# main.net
KiCad netlist of a schematic drawn in Altium Designer
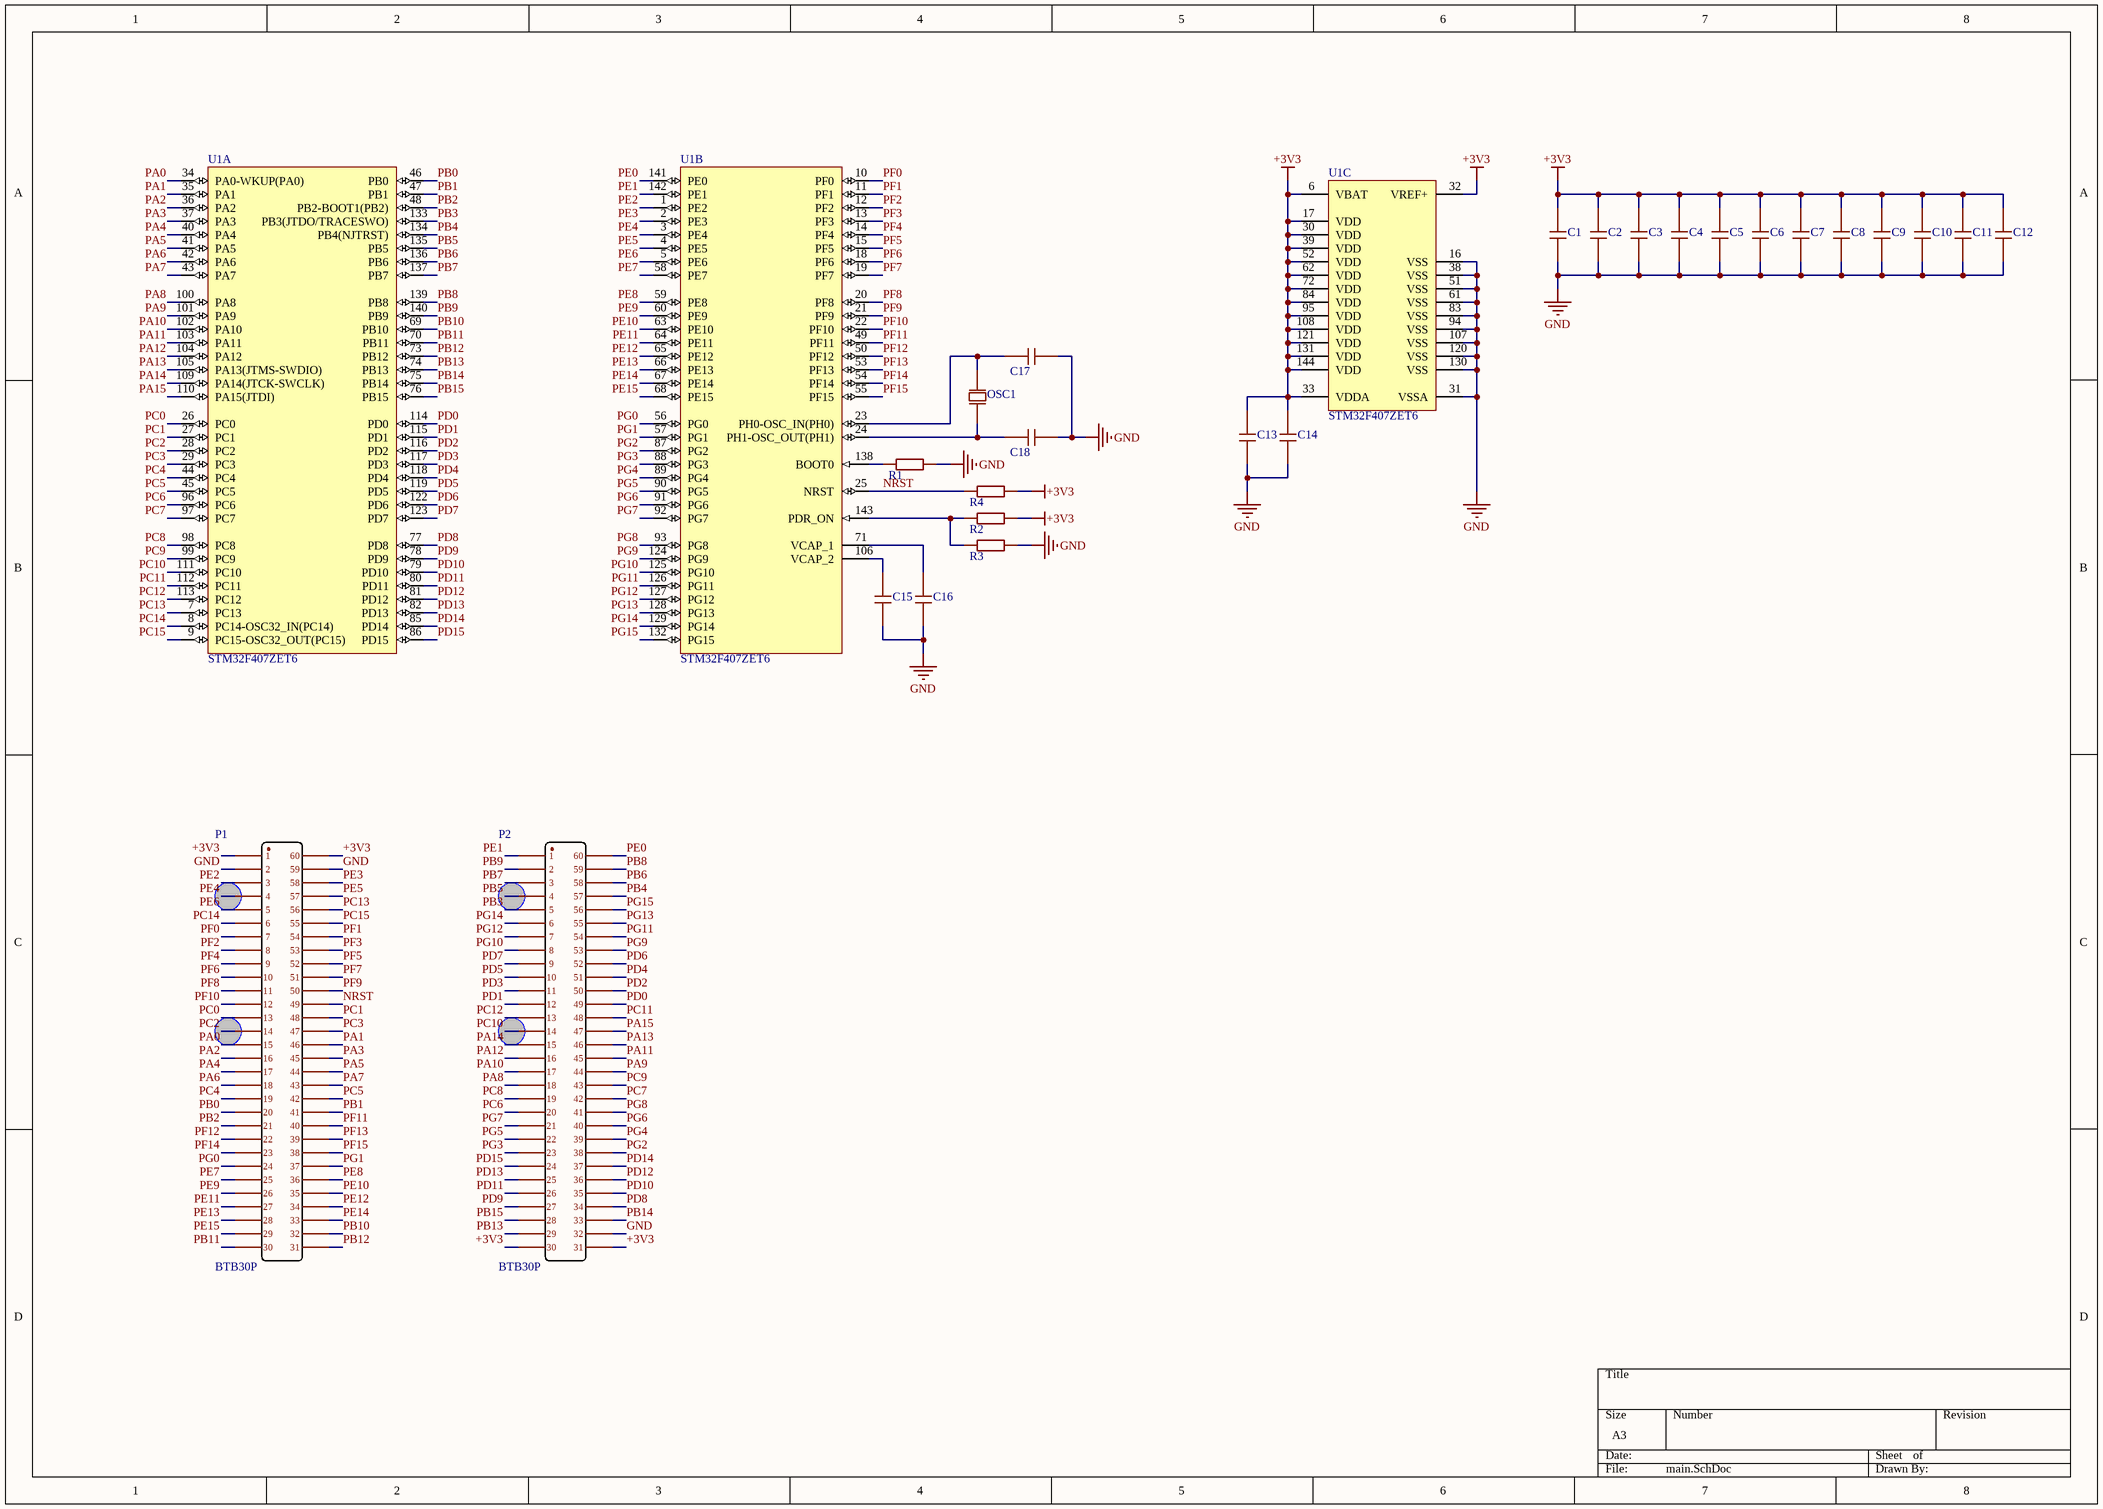
[diagram p0: main.SchDoc]

(export (version "E")
  (design (tool "Eeschema 10.0.6"))
  (components
    (comp (ref "C1") (value "100nF") (footprint "0603C") (libsource (lib "元件库") (part "电容_贴片")))
    (comp (ref "C2") (value "100nF") (footprint "0603C") (libsource (lib "元件库") (part "电容_贴片")))
    (comp (ref "C3") (value "100nF") (footprint "0603C") (libsource (lib "元件库") (part "电容_贴片")))
    (comp (ref "C4") (value "100nF") (footprint "0603C") (libsource (lib "元件库") (part "电容_贴片")))
    (comp (ref "C5") (value "100nF") (footprint "0603C") (libsource (lib "元件库") (part "电容_贴片")))
    (comp (ref "C6") (value "100nF") (footprint "0603C") (libsource (lib "元件库") (part "电容_贴片")))
    (comp (ref "C7") (value "100nF") (footprint "0603C") (libsource (lib "元件库") (part "电容_贴片")))
    (comp (ref "C8") (value "100nF") (footprint "0603C") (libsource (lib "元件库") (part "电容_贴片")))
    (comp (ref "C9") (value "100nF") (footprint "0603C") (libsource (lib "元件库") (part "电容_贴片")))
    (comp (ref "C10") (value "100nF") (footprint "0603C") (libsource (lib "元件库") (part "电容_贴片")))
    (comp (ref "C11") (value "100nF") (footprint "0603C") (libsource (lib "元件库") (part "电容_贴片")))
    (comp (ref "C12") (value "100nF") (footprint "0603C") (libsource (lib "元件库") (part "电容_贴片")))
    (comp (ref "C13") (value "10uF") (footprint "0603C") (libsource (lib "元件库") (part "电容_贴片")))
    (comp (ref "C14") (value "100nF") (footprint "0603C") (libsource (lib "元件库") (part "电容_贴片")))
    (comp (ref "C15") (value "2.2uF") (footprint "0603C") (libsource (lib "元件库") (part "电容_贴片")))
    (comp (ref "C16") (value "2.2uF") (footprint "0603C") (libsource (lib "元件库") (part "电容_贴片")))
    (comp (ref "C17") (value "20pF") (footprint "0603C") (libsource (lib "元件库") (part "电容_贴片")))
    (comp (ref "C18") (value "20pF") (footprint "0603C") (libsource (lib "元件库") (part "电容_贴片")))
    (comp (ref "OSC1") (value "晶振") (footprint "OSC_Passive_4P_3225") (libsource (lib "元件库") (part "晶振_无源")))
    (comp (ref "P1") (value "BTB30P") (footprint "BTB_F_30*2*0.8mm") (libsource (lib "接口库") (part "接插件2*30")))
    (comp (ref "P2") (value "BTB30P") (footprint "BTB_F_30*2*0.8mm") (libsource (lib "接口库") (part "接插件2*30")))
    (comp (ref "R1") (value "10K") (footprint "0603R") (libsource (lib "元件库") (part "电阻_贴片")))
    (comp (ref "R2") (value "10K") (footprint "0603R") (libsource (lib "元件库") (part "电阻_贴片")))
    (comp (ref "R3") (value "NC") (footprint "0603R") (libsource (lib "元件库") (part "电阻_贴片")))
    (comp (ref "R4") (value "10K") (footprint "0603R") (libsource (lib "元件库") (part "电阻_贴片")))
    (comp (ref "U1")
      (value "STM32F407ZET6")
      (footprint "STM-LQFP144")
      (fields (field (name "MANUFACTURER") "STMicroelectronics"))
      (libsource (lib "MCU库") (part "STM32F407ZET6"))
    )
  )
  (nets
    (net (code "1") (name "+3V3") (class "Default")
      (node (ref "C1") (pin "2") (pinfunction "2_2") (pintype "passive"))
      (node (ref "C10") (pin "2") (pinfunction "2_2") (pintype "passive"))
      (node (ref "C11") (pin "2") (pinfunction "2_2") (pintype "passive"))
      (node (ref "C12") (pin "2") (pinfunction "2_2") (pintype "passive"))
      (node (ref "C13") (pin "2") (pinfunction "2_2") (pintype "passive"))
      (node (ref "C14") (pin "2") (pinfunction "2_2") (pintype "passive"))
      (node (ref "C2") (pin "2") (pinfunction "2_2") (pintype "passive"))
      (node (ref "C3") (pin "2") (pinfunction "2_2") (pintype "passive"))
      (node (ref "C4") (pin "2") (pinfunction "2_2") (pintype "passive"))
      (node (ref "C5") (pin "2") (pinfunction "2_2") (pintype "passive"))
      (node (ref "C6") (pin "2") (pinfunction "2_2") (pintype "passive"))
      (node (ref "C7") (pin "2") (pinfunction "2_2") (pintype "passive"))
      (node (ref "C8") (pin "2") (pinfunction "2_2") (pintype "passive"))
      (node (ref "C9") (pin "2") (pinfunction "2_2") (pintype "passive"))
      (node (ref "P1") (pin "1") (pinfunction "1_1") (pintype "passive"))
      (node (ref "P1") (pin "60") (pinfunction "60_60") (pintype "passive"))
      (node (ref "P2") (pin "30") (pinfunction "30_30") (pintype "passive"))
      (node (ref "P2") (pin "31") (pinfunction "31_31") (pintype "passive"))
      (node (ref "R2") (pin "2") (pinfunction "2_2") (pintype "passive"))
      (node (ref "R4") (pin "2") (pinfunction "2_2") (pintype "passive"))
      (node (ref "U1") (pin "108") (pinfunction "VDD_108") (pintype "power_in"))
      (node (ref "U1") (pin "121") (pinfunction "VDD_121") (pintype "power_in"))
      (node (ref "U1") (pin "131") (pinfunction "VDD_131") (pintype "power_in"))
      (node (ref "U1") (pin "144") (pinfunction "VDD_144") (pintype "power_in"))
      (node (ref "U1") (pin "17") (pinfunction "VDD_17") (pintype "power_in"))
      (node (ref "U1") (pin "30") (pinfunction "VDD_30") (pintype "power_in"))
      (node (ref "U1") (pin "32") (pinfunction "VREF+_32") (pintype "power_in"))
      (node (ref "U1") (pin "33") (pinfunction "VDDA_33") (pintype "power_in"))
      (node (ref "U1") (pin "39") (pinfunction "VDD_39") (pintype "power_in"))
      (node (ref "U1") (pin "52") (pinfunction "VDD_52") (pintype "power_in"))
      (node (ref "U1") (pin "6") (pinfunction "VBAT_6") (pintype "power_in"))
      (node (ref "U1") (pin "62") (pinfunction "VDD_62") (pintype "power_in"))
      (node (ref "U1") (pin "72") (pinfunction "VDD_72") (pintype "power_in"))
      (node (ref "U1") (pin "84") (pinfunction "VDD_84") (pintype "power_in"))
      (node (ref "U1") (pin "95") (pinfunction "VDD_95") (pintype "power_in"))
    )
    (net (code "2") (name "/NRST") (class "Default")
      (node (ref "P1") (pin "49") (pinfunction "49_49") (pintype "passive"))
      (node (ref "R4") (pin "1") (pinfunction "1_1") (pintype "passive"))
      (node (ref "U1") (pin "25") (pinfunction "NRST_25") (pintype "bidirectional"))
    )
    (net (code "3") (name "/PA0") (class "Default")
      (node (ref "P1") (pin "15") (pinfunction "15_15") (pintype "passive"))
      (node (ref "U1") (pin "34") (pinfunction "PA0-WKUP(PA0)_34") (pintype "bidirectional"))
    )
    (net (code "4") (name "/PA1") (class "Default")
      (node (ref "P1") (pin "46") (pinfunction "46_46") (pintype "passive"))
      (node (ref "U1") (pin "35") (pinfunction "PA1_35") (pintype "bidirectional"))
    )
    (net (code "5") (name "/PA2") (class "Default")
      (node (ref "P1") (pin "16") (pinfunction "16_16") (pintype "passive"))
      (node (ref "U1") (pin "36") (pinfunction "PA2_36") (pintype "bidirectional"))
    )
    (net (code "6") (name "/PA3") (class "Default")
      (node (ref "P1") (pin "45") (pinfunction "45_45") (pintype "passive"))
      (node (ref "U1") (pin "37") (pinfunction "PA3_37") (pintype "bidirectional"))
    )
    (net (code "7") (name "/PA4") (class "Default")
      (node (ref "P1") (pin "17") (pinfunction "17_17") (pintype "passive"))
      (node (ref "U1") (pin "40") (pinfunction "PA4_40") (pintype "bidirectional"))
    )
    (net (code "8") (name "/PA5") (class "Default")
      (node (ref "P1") (pin "44") (pinfunction "44_44") (pintype "passive"))
      (node (ref "U1") (pin "41") (pinfunction "PA5_41") (pintype "bidirectional"))
    )
    (net (code "9") (name "/PA6") (class "Default")
      (node (ref "P1") (pin "18") (pinfunction "18_18") (pintype "passive"))
      (node (ref "U1") (pin "42") (pinfunction "PA6_42") (pintype "bidirectional"))
    )
    (net (code "10") (name "/PA7") (class "Default")
      (node (ref "P1") (pin "43") (pinfunction "43_43") (pintype "passive"))
      (node (ref "U1") (pin "43") (pinfunction "PA7_43") (pintype "bidirectional"))
    )
    (net (code "11") (name "/PA8") (class "Default")
      (node (ref "P2") (pin "18") (pinfunction "18_18") (pintype "passive"))
      (node (ref "U1") (pin "100") (pinfunction "PA8_100") (pintype "bidirectional"))
    )
    (net (code "12") (name "/PA9") (class "Default")
      (node (ref "P2") (pin "44") (pinfunction "44_44") (pintype "passive"))
      (node (ref "U1") (pin "101") (pinfunction "PA9_101") (pintype "bidirectional"))
    )
    (net (code "13") (name "/PA10") (class "Default")
      (node (ref "P2") (pin "17") (pinfunction "17_17") (pintype "passive"))
      (node (ref "U1") (pin "102") (pinfunction "PA10_102") (pintype "bidirectional"))
    )
    (net (code "14") (name "/PA11") (class "Default")
      (node (ref "P2") (pin "45") (pinfunction "45_45") (pintype "passive"))
      (node (ref "U1") (pin "103") (pinfunction "PA11_103") (pintype "bidirectional"))
    )
    (net (code "15") (name "/PA12") (class "Default")
      (node (ref "P2") (pin "16") (pinfunction "16_16") (pintype "passive"))
      (node (ref "U1") (pin "104") (pinfunction "PA12_104") (pintype "bidirectional"))
    )
    (net (code "16") (name "/PA13") (class "Default")
      (node (ref "P2") (pin "46") (pinfunction "46_46") (pintype "passive"))
      (node (ref "U1") (pin "105") (pinfunction "PA13(JTMS-SWDIO)_105") (pintype "bidirectional"))
    )
    (net (code "17") (name "/PA14") (class "Default")
      (node (ref "P2") (pin "15") (pinfunction "15_15") (pintype "passive"))
      (node (ref "U1") (pin "109") (pinfunction "PA14(JTCK-SWCLK)_109") (pintype "bidirectional"))
    )
    (net (code "18") (name "/PA15") (class "Default")
      (node (ref "P2") (pin "47") (pinfunction "47_47") (pintype "passive"))
      (node (ref "U1") (pin "110") (pinfunction "PA15(JTDI)_110") (pintype "bidirectional"))
    )
    (net (code "19") (name "/PB0") (class "Default")
      (node (ref "P1") (pin "20") (pinfunction "20_20") (pintype "passive"))
      (node (ref "U1") (pin "46") (pinfunction "PB0_46") (pintype "bidirectional"))
    )
    (net (code "20") (name "/PB1") (class "Default")
      (node (ref "P1") (pin "41") (pinfunction "41_41") (pintype "passive"))
      (node (ref "U1") (pin "47") (pinfunction "PB1_47") (pintype "bidirectional"))
    )
    (net (code "21") (name "/PB2") (class "Default")
      (node (ref "P1") (pin "21") (pinfunction "21_21") (pintype "passive"))
      (node (ref "U1") (pin "48") (pinfunction "PB2-BOOT1(PB2)_48") (pintype "bidirectional"))
    )
    (net (code "22") (name "/PB3") (class "Default")
      (node (ref "P2") (pin "5") (pinfunction "5_5") (pintype "passive"))
      (node (ref "U1") (pin "133") (pinfunction "PB3(JTDO/TRACESWO)_133") (pintype "bidirectional"))
    )
    (net (code "23") (name "/PB4") (class "Default")
      (node (ref "P2") (pin "57") (pinfunction "57_57") (pintype "passive"))
      (node (ref "U1") (pin "134") (pinfunction "PB4(NJTRST)_134") (pintype "bidirectional"))
    )
    (net (code "24") (name "/PB5") (class "Default")
      (node (ref "P2") (pin "4") (pinfunction "4_4") (pintype "passive"))
      (node (ref "U1") (pin "135") (pinfunction "PB5_135") (pintype "bidirectional"))
    )
    (net (code "25") (name "/PB6") (class "Default")
      (node (ref "P2") (pin "58") (pinfunction "58_58") (pintype "passive"))
      (node (ref "U1") (pin "136") (pinfunction "PB6_136") (pintype "bidirectional"))
    )
    (net (code "26") (name "/PB7") (class "Default")
      (node (ref "P2") (pin "3") (pinfunction "3_3") (pintype "passive"))
      (node (ref "U1") (pin "137") (pinfunction "PB7_137") (pintype "bidirectional"))
    )
    (net (code "27") (name "/PB8") (class "Default")
      (node (ref "P2") (pin "59") (pinfunction "59_59") (pintype "passive"))
      (node (ref "U1") (pin "139") (pinfunction "PB8_139") (pintype "bidirectional"))
    )
    (net (code "28") (name "/PB9") (class "Default")
      (node (ref "P2") (pin "2") (pinfunction "2_2") (pintype "passive"))
      (node (ref "U1") (pin "140") (pinfunction "PB9_140") (pintype "bidirectional"))
    )
    (net (code "29") (name "/PB10") (class "Default")
      (node (ref "P1") (pin "32") (pinfunction "32_32") (pintype "passive"))
      (node (ref "U1") (pin "69") (pinfunction "PB10_69") (pintype "bidirectional"))
    )
    (net (code "30") (name "/PB11") (class "Default")
      (node (ref "P1") (pin "30") (pinfunction "30_30") (pintype "passive"))
      (node (ref "U1") (pin "70") (pinfunction "PB11_70") (pintype "bidirectional"))
    )
    (net (code "31") (name "/PB12") (class "Default")
      (node (ref "P1") (pin "31") (pinfunction "31_31") (pintype "passive"))
      (node (ref "U1") (pin "73") (pinfunction "PB12_73") (pintype "bidirectional"))
    )
    (net (code "32") (name "/PB13") (class "Default")
      (node (ref "P2") (pin "29") (pinfunction "29_29") (pintype "passive"))
      (node (ref "U1") (pin "74") (pinfunction "PB13_74") (pintype "bidirectional"))
    )
    (net (code "33") (name "/PB14") (class "Default")
      (node (ref "P2") (pin "33") (pinfunction "33_33") (pintype "passive"))
      (node (ref "U1") (pin "75") (pinfunction "PB14_75") (pintype "bidirectional"))
    )
    (net (code "34") (name "/PB15") (class "Default")
      (node (ref "P2") (pin "28") (pinfunction "28_28") (pintype "passive"))
      (node (ref "U1") (pin "76") (pinfunction "PB15_76") (pintype "bidirectional"))
    )
    (net (code "35") (name "/PC0") (class "Default")
      (node (ref "P1") (pin "13") (pinfunction "13_13") (pintype "passive"))
      (node (ref "U1") (pin "26") (pinfunction "PC0_26") (pintype "bidirectional"))
    )
    (net (code "36") (name "/PC1") (class "Default")
      (node (ref "P1") (pin "48") (pinfunction "48_48") (pintype "passive"))
      (node (ref "U1") (pin "27") (pinfunction "PC1_27") (pintype "bidirectional"))
    )
    (net (code "37") (name "/PC2") (class "Default")
      (node (ref "P1") (pin "14") (pinfunction "14_14") (pintype "passive"))
      (node (ref "U1") (pin "28") (pinfunction "PC2_28") (pintype "bidirectional"))
    )
    (net (code "38") (name "/PC3") (class "Default")
      (node (ref "P1") (pin "47") (pinfunction "47_47") (pintype "passive"))
      (node (ref "U1") (pin "29") (pinfunction "PC3_29") (pintype "bidirectional"))
    )
    (net (code "39") (name "/PC4") (class "Default")
      (node (ref "P1") (pin "19") (pinfunction "19_19") (pintype "passive"))
      (node (ref "U1") (pin "44") (pinfunction "PC4_44") (pintype "bidirectional"))
    )
    (net (code "40") (name "/PC5") (class "Default")
      (node (ref "P1") (pin "42") (pinfunction "42_42") (pintype "passive"))
      (node (ref "U1") (pin "45") (pinfunction "PC5_45") (pintype "bidirectional"))
    )
    (net (code "41") (name "/PC6") (class "Default")
      (node (ref "P2") (pin "20") (pinfunction "20_20") (pintype "passive"))
      (node (ref "U1") (pin "96") (pinfunction "PC6_96") (pintype "bidirectional"))
    )
    (net (code "42") (name "/PC7") (class "Default")
      (node (ref "P2") (pin "42") (pinfunction "42_42") (pintype "passive"))
      (node (ref "U1") (pin "97") (pinfunction "PC7_97") (pintype "bidirectional"))
    )
    (net (code "43") (name "/PC8") (class "Default")
      (node (ref "P2") (pin "19") (pinfunction "19_19") (pintype "passive"))
      (node (ref "U1") (pin "98") (pinfunction "PC8_98") (pintype "bidirectional"))
    )
    (net (code "44") (name "/PC9") (class "Default")
      (node (ref "P2") (pin "43") (pinfunction "43_43") (pintype "passive"))
      (node (ref "U1") (pin "99") (pinfunction "PC9_99") (pintype "bidirectional"))
    )
    (net (code "45") (name "/PC10") (class "Default")
      (node (ref "P2") (pin "14") (pinfunction "14_14") (pintype "passive"))
      (node (ref "U1") (pin "111") (pinfunction "PC10_111") (pintype "bidirectional"))
    )
    (net (code "46") (name "/PC11") (class "Default")
      (node (ref "P2") (pin "48") (pinfunction "48_48") (pintype "passive"))
      (node (ref "U1") (pin "112") (pinfunction "PC11_112") (pintype "bidirectional"))
    )
    (net (code "47") (name "/PC12") (class "Default")
      (node (ref "P2") (pin "13") (pinfunction "13_13") (pintype "passive"))
      (node (ref "U1") (pin "113") (pinfunction "PC12_113") (pintype "bidirectional"))
    )
    (net (code "48") (name "/PC13") (class "Default")
      (node (ref "P1") (pin "56") (pinfunction "56_56") (pintype "passive"))
      (node (ref "U1") (pin "7") (pinfunction "PC13_7") (pintype "bidirectional"))
    )
    (net (code "49") (name "/PC14") (class "Default")
      (node (ref "P1") (pin "6") (pinfunction "6_6") (pintype "passive"))
      (node (ref "U1") (pin "8") (pinfunction "PC14-OSC32_IN(PC14)_8") (pintype "bidirectional"))
    )
    (net (code "50") (name "/PC15") (class "Default")
      (node (ref "P1") (pin "55") (pinfunction "55_55") (pintype "passive"))
      (node (ref "U1") (pin "9") (pinfunction "PC15-OSC32_OUT(PC15)_9") (pintype "bidirectional"))
    )
    (net (code "51") (name "/PD0") (class "Default")
      (node (ref "P2") (pin "49") (pinfunction "49_49") (pintype "passive"))
      (node (ref "U1") (pin "114") (pinfunction "PD0_114") (pintype "bidirectional"))
    )
    (net (code "52") (name "/PD1") (class "Default")
      (node (ref "P2") (pin "12") (pinfunction "12_12") (pintype "passive"))
      (node (ref "U1") (pin "115") (pinfunction "PD1_115") (pintype "bidirectional"))
    )
    (net (code "53") (name "/PD2") (class "Default")
      (node (ref "P2") (pin "50") (pinfunction "50_50") (pintype "passive"))
      (node (ref "U1") (pin "116") (pinfunction "PD2_116") (pintype "bidirectional"))
    )
    (net (code "54") (name "/PD3") (class "Default")
      (node (ref "P2") (pin "11") (pinfunction "11_11") (pintype "passive"))
      (node (ref "U1") (pin "117") (pinfunction "PD3_117") (pintype "bidirectional"))
    )
    (net (code "55") (name "/PD4") (class "Default")
      (node (ref "P2") (pin "51") (pinfunction "51_51") (pintype "passive"))
      (node (ref "U1") (pin "118") (pinfunction "PD4_118") (pintype "bidirectional"))
    )
    (net (code "56") (name "/PD5") (class "Default")
      (node (ref "P2") (pin "10") (pinfunction "10_10") (pintype "passive"))
      (node (ref "U1") (pin "119") (pinfunction "PD5_119") (pintype "bidirectional"))
    )
    (net (code "57") (name "/PD6") (class "Default")
      (node (ref "P2") (pin "52") (pinfunction "52_52") (pintype "passive"))
      (node (ref "U1") (pin "122") (pinfunction "PD6_122") (pintype "bidirectional"))
    )
    (net (code "58") (name "/PD7") (class "Default")
      (node (ref "P2") (pin "9") (pinfunction "9_9") (pintype "passive"))
      (node (ref "U1") (pin "123") (pinfunction "PD7_123") (pintype "bidirectional"))
    )
    (net (code "59") (name "/PD8") (class "Default")
      (node (ref "P2") (pin "34") (pinfunction "34_34") (pintype "passive"))
      (node (ref "U1") (pin "77") (pinfunction "PD8_77") (pintype "bidirectional"))
    )
    (net (code "60") (name "/PD9") (class "Default")
      (node (ref "P2") (pin "27") (pinfunction "27_27") (pintype "passive"))
      (node (ref "U1") (pin "78") (pinfunction "PD9_78") (pintype "bidirectional"))
    )
    (net (code "61") (name "/PD10") (class "Default")
      (node (ref "P2") (pin "35") (pinfunction "35_35") (pintype "passive"))
      (node (ref "U1") (pin "79") (pinfunction "PD10_79") (pintype "bidirectional"))
    )
    (net (code "62") (name "/PD11") (class "Default")
      (node (ref "P2") (pin "26") (pinfunction "26_26") (pintype "passive"))
      (node (ref "U1") (pin "80") (pinfunction "PD11_80") (pintype "bidirectional"))
    )
    (net (code "63") (name "/PD12") (class "Default")
      (node (ref "P2") (pin "36") (pinfunction "36_36") (pintype "passive"))
      (node (ref "U1") (pin "81") (pinfunction "PD12_81") (pintype "bidirectional"))
    )
    (net (code "64") (name "/PD13") (class "Default")
      (node (ref "P2") (pin "25") (pinfunction "25_25") (pintype "passive"))
      (node (ref "U1") (pin "82") (pinfunction "PD13_82") (pintype "bidirectional"))
    )
    (net (code "65") (name "/PD14") (class "Default")
      (node (ref "P2") (pin "37") (pinfunction "37_37") (pintype "passive"))
      (node (ref "U1") (pin "85") (pinfunction "PD14_85") (pintype "bidirectional"))
    )
    (net (code "66") (name "/PD15") (class "Default")
      (node (ref "P2") (pin "24") (pinfunction "24_24") (pintype "passive"))
      (node (ref "U1") (pin "86") (pinfunction "PD15_86") (pintype "bidirectional"))
    )
    (net (code "67") (name "/PE0") (class "Default")
      (node (ref "P2") (pin "60") (pinfunction "60_60") (pintype "passive"))
      (node (ref "U1") (pin "141") (pinfunction "PE0_141") (pintype "bidirectional"))
    )
    (net (code "68") (name "/PE1") (class "Default")
      (node (ref "P2") (pin "1") (pinfunction "1_1") (pintype "passive"))
      (node (ref "U1") (pin "142") (pinfunction "PE1_142") (pintype "bidirectional"))
    )
    (net (code "69") (name "/PE2") (class "Default")
      (node (ref "P1") (pin "3") (pinfunction "3_3") (pintype "passive"))
      (node (ref "U1") (pin "1") (pinfunction "PE2_1") (pintype "bidirectional"))
    )
    (net (code "70") (name "/PE3") (class "Default")
      (node (ref "P1") (pin "58") (pinfunction "58_58") (pintype "passive"))
      (node (ref "U1") (pin "2") (pinfunction "PE3_2") (pintype "bidirectional"))
    )
    (net (code "71") (name "/PE4") (class "Default")
      (node (ref "P1") (pin "4") (pinfunction "4_4") (pintype "passive"))
      (node (ref "U1") (pin "3") (pinfunction "PE4_3") (pintype "bidirectional"))
    )
    (net (code "72") (name "/PE5") (class "Default")
      (node (ref "P1") (pin "57") (pinfunction "57_57") (pintype "passive"))
      (node (ref "U1") (pin "4") (pinfunction "PE5_4") (pintype "bidirectional"))
    )
    (net (code "73") (name "/PE6") (class "Default")
      (node (ref "P1") (pin "5") (pinfunction "5_5") (pintype "passive"))
      (node (ref "U1") (pin "5") (pinfunction "PE6_5") (pintype "bidirectional"))
    )
    (net (code "74") (name "/PE7") (class "Default")
      (node (ref "P1") (pin "25") (pinfunction "25_25") (pintype "passive"))
      (node (ref "U1") (pin "58") (pinfunction "PE7_58") (pintype "bidirectional"))
    )
    (net (code "75") (name "/PE8") (class "Default")
      (node (ref "P1") (pin "36") (pinfunction "36_36") (pintype "passive"))
      (node (ref "U1") (pin "59") (pinfunction "PE8_59") (pintype "bidirectional"))
    )
    (net (code "76") (name "/PE9") (class "Default")
      (node (ref "P1") (pin "26") (pinfunction "26_26") (pintype "passive"))
      (node (ref "U1") (pin "60") (pinfunction "PE9_60") (pintype "bidirectional"))
    )
    (net (code "77") (name "/PE10") (class "Default")
      (node (ref "P1") (pin "35") (pinfunction "35_35") (pintype "passive"))
      (node (ref "U1") (pin "63") (pinfunction "PE10_63") (pintype "bidirectional"))
    )
    (net (code "78") (name "/PE11") (class "Default")
      (node (ref "P1") (pin "27") (pinfunction "27_27") (pintype "passive"))
      (node (ref "U1") (pin "64") (pinfunction "PE11_64") (pintype "bidirectional"))
    )
    (net (code "79") (name "/PE12") (class "Default")
      (node (ref "P1") (pin "34") (pinfunction "34_34") (pintype "passive"))
      (node (ref "U1") (pin "65") (pinfunction "PE12_65") (pintype "bidirectional"))
    )
    (net (code "80") (name "/PE13") (class "Default")
      (node (ref "P1") (pin "28") (pinfunction "28_28") (pintype "passive"))
      (node (ref "U1") (pin "66") (pinfunction "PE13_66") (pintype "bidirectional"))
    )
    (net (code "81") (name "/PE14") (class "Default")
      (node (ref "P1") (pin "33") (pinfunction "33_33") (pintype "passive"))
      (node (ref "U1") (pin "67") (pinfunction "PE14_67") (pintype "bidirectional"))
    )
    (net (code "82") (name "/PE15") (class "Default")
      (node (ref "P1") (pin "29") (pinfunction "29_29") (pintype "passive"))
      (node (ref "U1") (pin "68") (pinfunction "PE15_68") (pintype "bidirectional"))
    )
    (net (code "83") (name "/PF0") (class "Default")
      (node (ref "P1") (pin "7") (pinfunction "7_7") (pintype "passive"))
      (node (ref "U1") (pin "10") (pinfunction "PF0_10") (pintype "bidirectional"))
    )
    (net (code "84") (name "/PF1") (class "Default")
      (node (ref "P1") (pin "54") (pinfunction "54_54") (pintype "passive"))
      (node (ref "U1") (pin "11") (pinfunction "PF1_11") (pintype "bidirectional"))
    )
    (net (code "85") (name "/PF2") (class "Default")
      (node (ref "P1") (pin "8") (pinfunction "8_8") (pintype "passive"))
      (node (ref "U1") (pin "12") (pinfunction "PF2_12") (pintype "bidirectional"))
    )
    (net (code "86") (name "/PF3") (class "Default")
      (node (ref "P1") (pin "53") (pinfunction "53_53") (pintype "passive"))
      (node (ref "U1") (pin "13") (pinfunction "PF3_13") (pintype "bidirectional"))
    )
    (net (code "87") (name "/PF4") (class "Default")
      (node (ref "P1") (pin "9") (pinfunction "9_9") (pintype "passive"))
      (node (ref "U1") (pin "14") (pinfunction "PF4_14") (pintype "bidirectional"))
    )
    (net (code "88") (name "/PF5") (class "Default")
      (node (ref "P1") (pin "52") (pinfunction "52_52") (pintype "passive"))
      (node (ref "U1") (pin "15") (pinfunction "PF5_15") (pintype "bidirectional"))
    )
    (net (code "89") (name "/PF6") (class "Default")
      (node (ref "P1") (pin "10") (pinfunction "10_10") (pintype "passive"))
      (node (ref "U1") (pin "18") (pinfunction "PF6_18") (pintype "bidirectional"))
    )
    (net (code "90") (name "/PF7") (class "Default")
      (node (ref "P1") (pin "51") (pinfunction "51_51") (pintype "passive"))
      (node (ref "U1") (pin "19") (pinfunction "PF7_19") (pintype "bidirectional"))
    )
    (net (code "91") (name "/PF8") (class "Default")
      (node (ref "P1") (pin "11") (pinfunction "11_11") (pintype "passive"))
      (node (ref "U1") (pin "20") (pinfunction "PF8_20") (pintype "bidirectional"))
    )
    (net (code "92") (name "/PF9") (class "Default")
      (node (ref "P1") (pin "50") (pinfunction "50_50") (pintype "passive"))
      (node (ref "U1") (pin "21") (pinfunction "PF9_21") (pintype "bidirectional"))
    )
    (net (code "93") (name "/PF10") (class "Default")
      (node (ref "P1") (pin "12") (pinfunction "12_12") (pintype "passive"))
      (node (ref "U1") (pin "22") (pinfunction "PF10_22") (pintype "bidirectional"))
    )
    (net (code "94") (name "/PF11") (class "Default")
      (node (ref "P1") (pin "40") (pinfunction "40_40") (pintype "passive"))
      (node (ref "U1") (pin "49") (pinfunction "PF11_49") (pintype "bidirectional"))
    )
    (net (code "95") (name "/PF12") (class "Default")
      (node (ref "P1") (pin "22") (pinfunction "22_22") (pintype "passive"))
      (node (ref "U1") (pin "50") (pinfunction "PF12_50") (pintype "bidirectional"))
    )
    (net (code "96") (name "/PF13") (class "Default")
      (node (ref "P1") (pin "39") (pinfunction "39_39") (pintype "passive"))
      (node (ref "U1") (pin "53") (pinfunction "PF13_53") (pintype "bidirectional"))
    )
    (net (code "97") (name "/PF14") (class "Default")
      (node (ref "P1") (pin "23") (pinfunction "23_23") (pintype "passive"))
      (node (ref "U1") (pin "54") (pinfunction "PF14_54") (pintype "bidirectional"))
    )
    (net (code "98") (name "/PF15") (class "Default")
      (node (ref "P1") (pin "38") (pinfunction "38_38") (pintype "passive"))
      (node (ref "U1") (pin "55") (pinfunction "PF15_55") (pintype "bidirectional"))
    )
    (net (code "99") (name "/PG0") (class "Default")
      (node (ref "P1") (pin "24") (pinfunction "24_24") (pintype "passive"))
      (node (ref "U1") (pin "56") (pinfunction "PG0_56") (pintype "bidirectional"))
    )
    (net (code "100") (name "/PG1") (class "Default")
      (node (ref "P1") (pin "37") (pinfunction "37_37") (pintype "passive"))
      (node (ref "U1") (pin "57") (pinfunction "PG1_57") (pintype "bidirectional"))
    )
    (net (code "101") (name "/PG2") (class "Default")
      (node (ref "P2") (pin "38") (pinfunction "38_38") (pintype "passive"))
      (node (ref "U1") (pin "87") (pinfunction "PG2_87") (pintype "bidirectional"))
    )
    (net (code "102") (name "/PG3") (class "Default")
      (node (ref "P2") (pin "23") (pinfunction "23_23") (pintype "passive"))
      (node (ref "U1") (pin "88") (pinfunction "PG3_88") (pintype "bidirectional"))
    )
    (net (code "103") (name "/PG4") (class "Default")
      (node (ref "P2") (pin "39") (pinfunction "39_39") (pintype "passive"))
      (node (ref "U1") (pin "89") (pinfunction "PG4_89") (pintype "bidirectional"))
    )
    (net (code "104") (name "/PG5") (class "Default")
      (node (ref "P2") (pin "22") (pinfunction "22_22") (pintype "passive"))
      (node (ref "U1") (pin "90") (pinfunction "PG5_90") (pintype "bidirectional"))
    )
    (net (code "105") (name "/PG6") (class "Default")
      (node (ref "P2") (pin "40") (pinfunction "40_40") (pintype "passive"))
      (node (ref "U1") (pin "91") (pinfunction "PG6_91") (pintype "bidirectional"))
    )
    (net (code "106") (name "/PG7") (class "Default")
      (node (ref "P2") (pin "21") (pinfunction "21_21") (pintype "passive"))
      (node (ref "U1") (pin "92") (pinfunction "PG7_92") (pintype "bidirectional"))
    )
    (net (code "107") (name "/PG8") (class "Default")
      (node (ref "P2") (pin "41") (pinfunction "41_41") (pintype "passive"))
      (node (ref "U1") (pin "93") (pinfunction "PG8_93") (pintype "bidirectional"))
    )
    (net (code "108") (name "/PG9") (class "Default")
      (node (ref "P2") (pin "53") (pinfunction "53_53") (pintype "passive"))
      (node (ref "U1") (pin "124") (pinfunction "PG9_124") (pintype "bidirectional"))
    )
    (net (code "109") (name "/PG10") (class "Default")
      (node (ref "P2") (pin "8") (pinfunction "8_8") (pintype "passive"))
      (node (ref "U1") (pin "125") (pinfunction "PG10_125") (pintype "bidirectional"))
    )
    (net (code "110") (name "/PG11") (class "Default")
      (node (ref "P2") (pin "54") (pinfunction "54_54") (pintype "passive"))
      (node (ref "U1") (pin "126") (pinfunction "PG11_126") (pintype "bidirectional"))
    )
    (net (code "111") (name "/PG12") (class "Default")
      (node (ref "P2") (pin "7") (pinfunction "7_7") (pintype "passive"))
      (node (ref "U1") (pin "127") (pinfunction "PG12_127") (pintype "bidirectional"))
    )
    (net (code "112") (name "/PG13") (class "Default")
      (node (ref "P2") (pin "55") (pinfunction "55_55") (pintype "passive"))
      (node (ref "U1") (pin "128") (pinfunction "PG13_128") (pintype "bidirectional"))
    )
    (net (code "113") (name "/PG14") (class "Default")
      (node (ref "P2") (pin "6") (pinfunction "6_6") (pintype "passive"))
      (node (ref "U1") (pin "129") (pinfunction "PG14_129") (pintype "bidirectional"))
    )
    (net (code "114") (name "/PG15") (class "Default")
      (node (ref "P2") (pin "56") (pinfunction "56_56") (pintype "passive"))
      (node (ref "U1") (pin "132") (pinfunction "PG15_132") (pintype "bidirectional"))
    )
    (net (code "115") (name "GND") (class "Default")
      (node (ref "C1") (pin "1") (pinfunction "1_1") (pintype "passive"))
      (node (ref "C10") (pin "1") (pinfunction "1_1") (pintype "passive"))
      (node (ref "C11") (pin "1") (pinfunction "1_1") (pintype "passive"))
      (node (ref "C12") (pin "1") (pinfunction "1_1") (pintype "passive"))
      (node (ref "C13") (pin "1") (pinfunction "1_1") (pintype "passive"))
      (node (ref "C14") (pin "1") (pinfunction "1_1") (pintype "passive"))
      (node (ref "C15") (pin "2") (pinfunction "2_2") (pintype "passive"))
      (node (ref "C16") (pin "2") (pinfunction "2_2") (pintype "passive"))
      (node (ref "C17") (pin "1") (pinfunction "1_1") (pintype "passive"))
      (node (ref "C18") (pin "1") (pinfunction "1_1") (pintype "passive"))
      (node (ref "C2") (pin "1") (pinfunction "1_1") (pintype "passive"))
      (node (ref "C3") (pin "1") (pinfunction "1_1") (pintype "passive"))
      (node (ref "C4") (pin "1") (pinfunction "1_1") (pintype "passive"))
      (node (ref "C5") (pin "1") (pinfunction "1_1") (pintype "passive"))
      (node (ref "C6") (pin "1") (pinfunction "1_1") (pintype "passive"))
      (node (ref "C7") (pin "1") (pinfunction "1_1") (pintype "passive"))
      (node (ref "C8") (pin "1") (pinfunction "1_1") (pintype "passive"))
      (node (ref "C9") (pin "1") (pinfunction "1_1") (pintype "passive"))
      (node (ref "P1") (pin "2") (pinfunction "2_2") (pintype "passive"))
      (node (ref "P1") (pin "59") (pinfunction "59_59") (pintype "passive"))
      (node (ref "P2") (pin "32") (pinfunction "32_32") (pintype "passive"))
      (node (ref "R1") (pin "2") (pinfunction "2_2") (pintype "passive"))
      (node (ref "R3") (pin "2") (pinfunction "2_2") (pintype "passive"))
      (node (ref "U1") (pin "107") (pinfunction "VSS_107") (pintype "power_in"))
      (node (ref "U1") (pin "120") (pinfunction "VSS_120") (pintype "power_in"))
      (node (ref "U1") (pin "130") (pinfunction "VSS_130") (pintype "power_in"))
      (node (ref "U1") (pin "16") (pinfunction "VSS_16") (pintype "power_in"))
      (node (ref "U1") (pin "31") (pinfunction "VSSA_31") (pintype "power_in"))
      (node (ref "U1") (pin "38") (pinfunction "VSS_38") (pintype "power_in"))
      (node (ref "U1") (pin "51") (pinfunction "VSS_51") (pintype "power_in"))
      (node (ref "U1") (pin "61") (pinfunction "VSS_61") (pintype "power_in"))
      (node (ref "U1") (pin "83") (pinfunction "VSS_83") (pintype "power_in"))
      (node (ref "U1") (pin "94") (pinfunction "VSS_94") (pintype "power_in"))
    )
    (net (code "116") (name "Net-(U1B-BOOT0)") (class "Default")
      (node (ref "R1") (pin "1") (pinfunction "1_1") (pintype "passive"))
      (node (ref "U1") (pin "138") (pinfunction "BOOT0_138") (pintype "input"))
    )
    (net (code "117") (name "Net-(U1B-PDR_ON)") (class "Default")
      (node (ref "R2") (pin "1") (pinfunction "1_1") (pintype "passive"))
      (node (ref "R3") (pin "1") (pinfunction "1_1") (pintype "passive"))
      (node (ref "U1") (pin "143") (pinfunction "PDR_ON_143") (pintype "input"))
    )
    (net (code "118") (name "Net-(U1B-PH0-OSC_IN(PH0))") (class "Default")
      (node (ref "C17") (pin "2") (pinfunction "2_2") (pintype "passive"))
      (node (ref "OSC1") (pin "2") (pinfunction "2_2") (pintype "passive"))
      (node (ref "U1") (pin "23") (pinfunction "PH0-OSC_IN(PH0)_23") (pintype "bidirectional"))
    )
    (net (code "119") (name "Net-(U1B-PH1-OSC_OUT(PH1))") (class "Default")
      (node (ref "C18") (pin "2") (pinfunction "2_2") (pintype "passive"))
      (node (ref "OSC1") (pin "1") (pinfunction "1_1") (pintype "passive"))
      (node (ref "U1") (pin "24") (pinfunction "PH1-OSC_OUT(PH1)_24") (pintype "bidirectional"))
    )
    (net (code "120") (name "Net-(U1B-VCAP_1)") (class "Default")
      (node (ref "C16") (pin "1") (pinfunction "1_1") (pintype "passive"))
      (node (ref "U1") (pin "71") (pinfunction "VCAP_1_71") (pintype "power_in"))
    )
    (net (code "121") (name "Net-(U1B-VCAP_2)") (class "Default")
      (node (ref "C15") (pin "1") (pinfunction "1_1") (pintype "passive"))
      (node (ref "U1") (pin "106") (pinfunction "VCAP_2_106") (pintype "power_in"))
    )
  )
)
